# SCH_USB-HUB_2024-08-30.net
KiCad netlist of a schematic drawn in EasyEDA
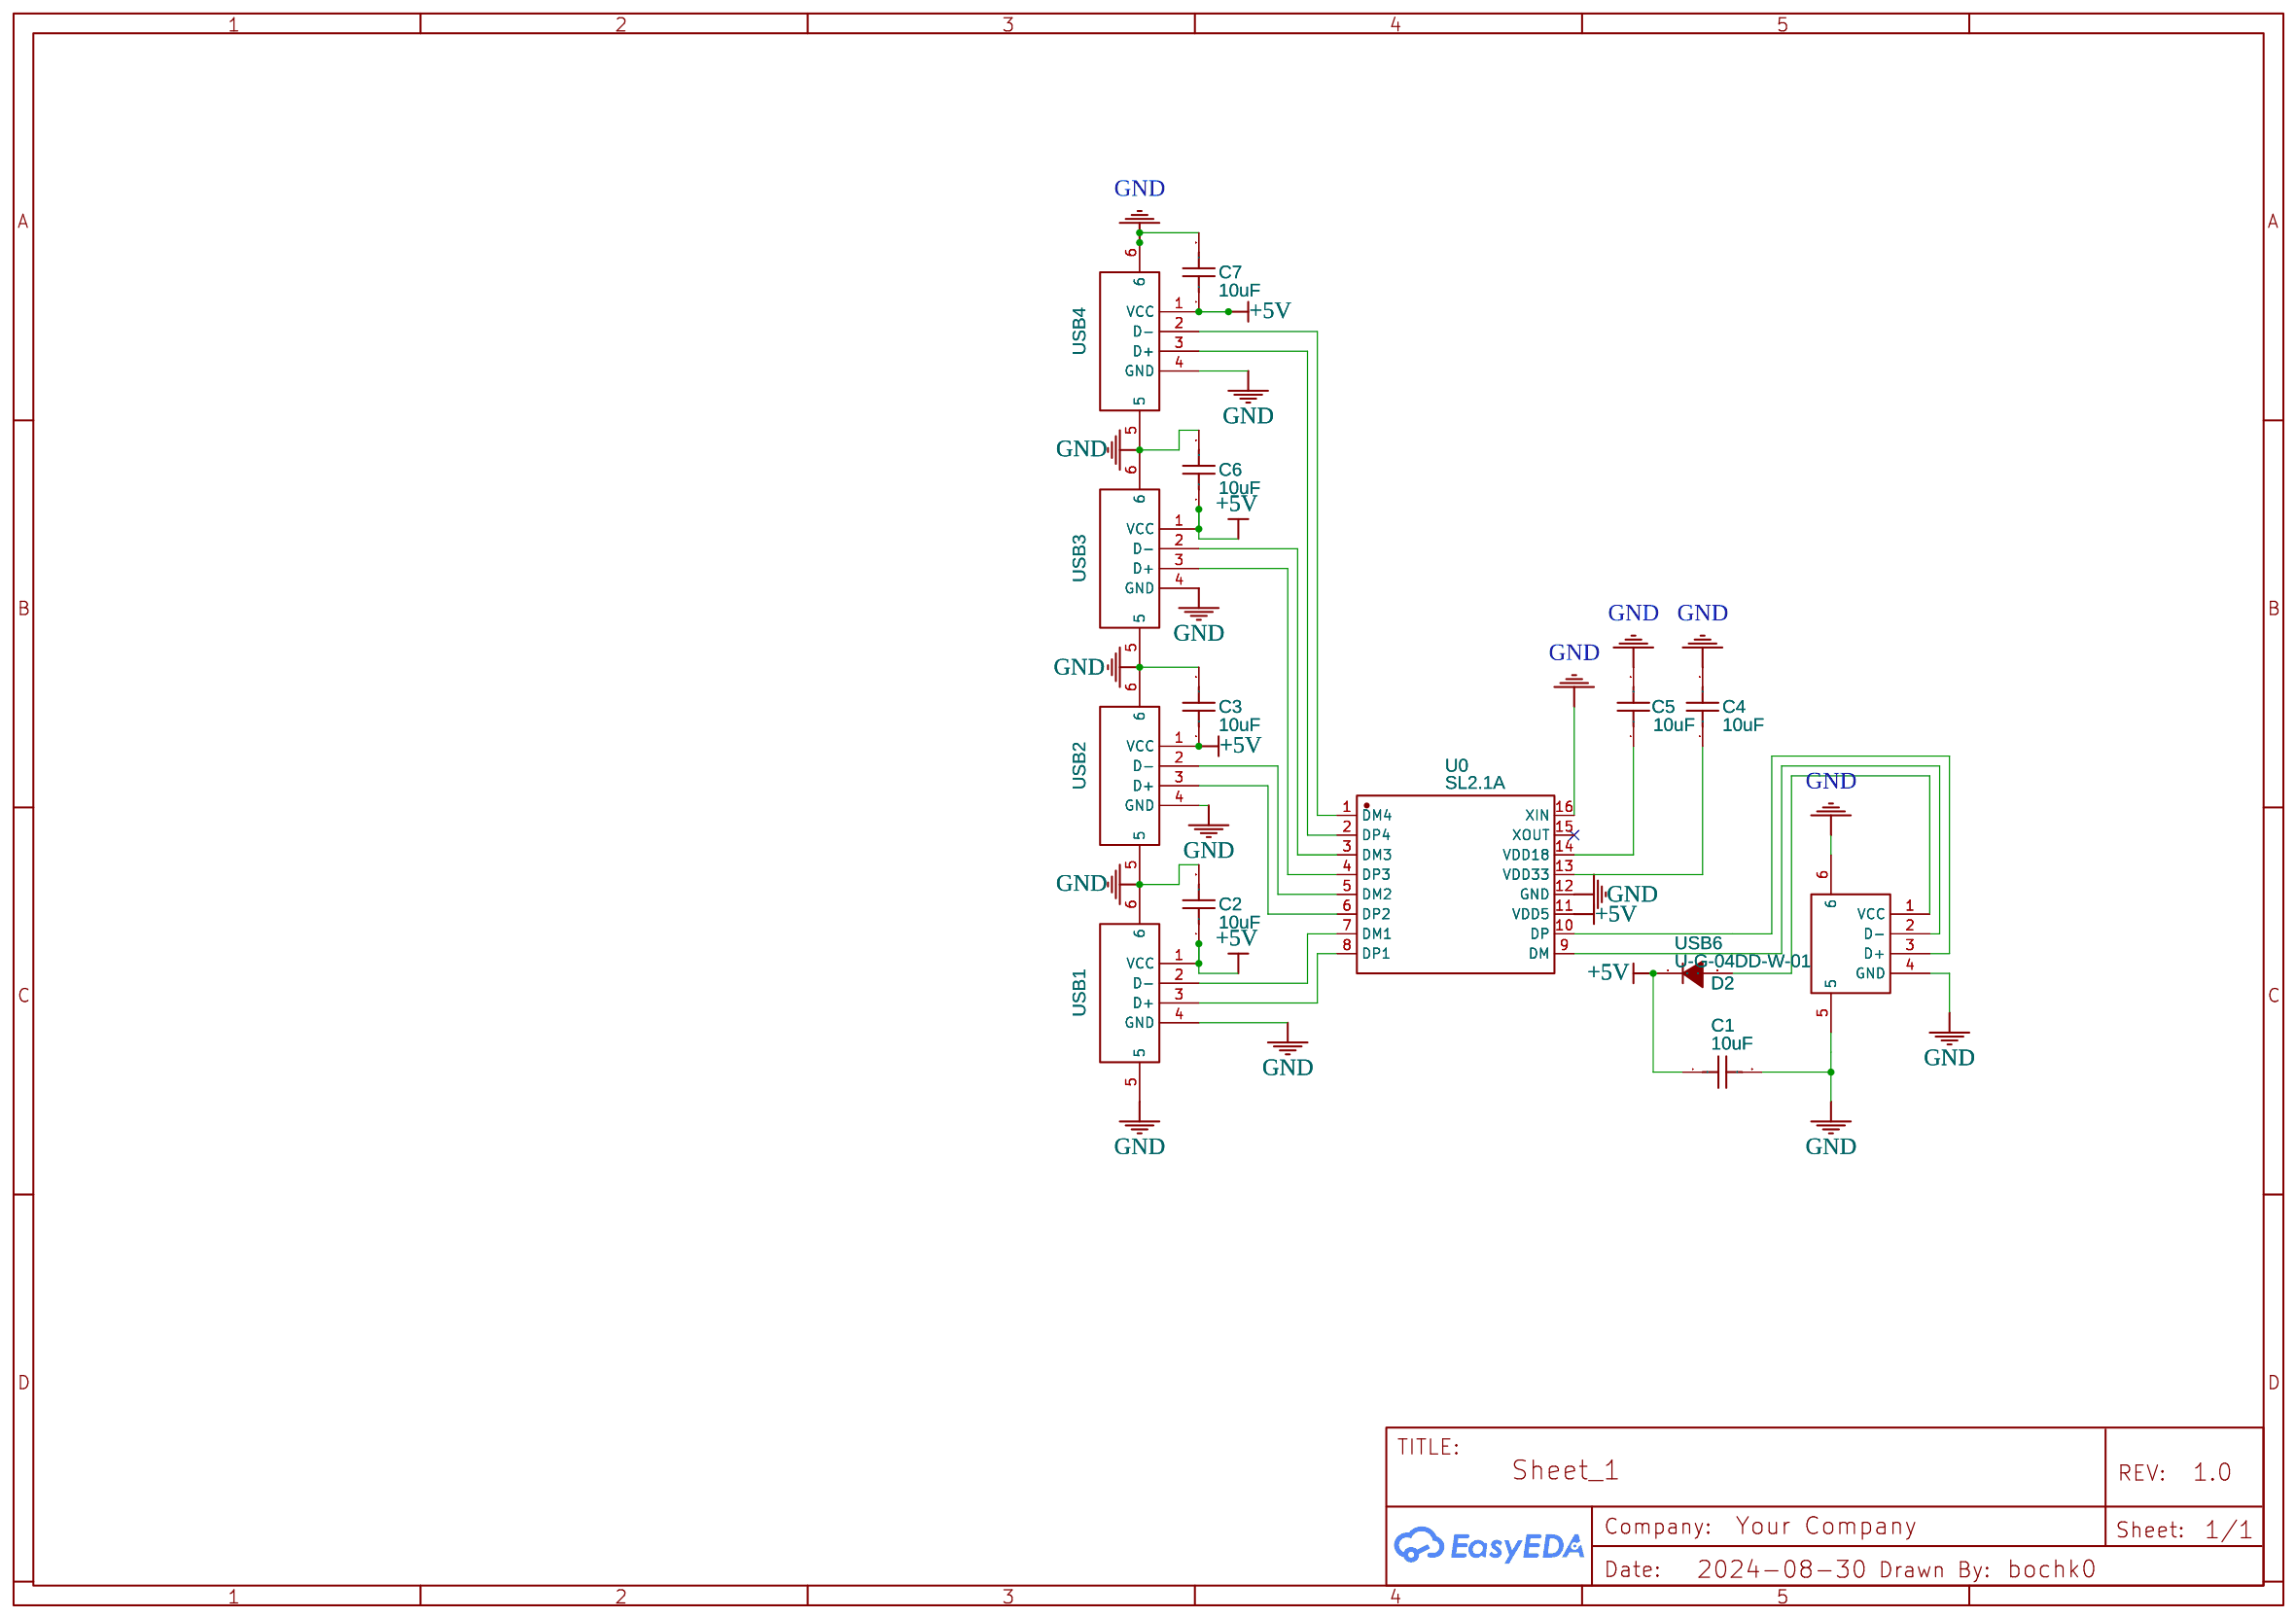
[diagram p0: schematic sheet]

(export (version "E")
  (design (tool "Eeschema 10.0.6"))
  (components
    (comp (ref "C1")
      (value "10uF")
      (fields
        (field (name "Manufacturer Part") "CL10A106KP8NNNC")
        (field (name "Manufacturer") "SAMSUNG(三星)")
      )
      (libsource (lib "") (part "CL10A106KP8NNNC_1"))
    )
    (comp (ref "C2")
      (value "10uF")
      (fields
        (field (name "Manufacturer Part") "CL10A106KP8NNNC")
        (field (name "Manufacturer") "SAMSUNG(三星)")
      )
      (libsource (lib "") (part "CL10A106KP8NNNC"))
    )
    (comp (ref "C3")
      (value "10uF")
      (fields
        (field (name "Manufacturer Part") "CL10A106KP8NNNC")
        (field (name "Manufacturer") "SAMSUNG(三星)")
      )
      (libsource (lib "") (part "CL10A106KP8NNNC"))
    )
    (comp (ref "C4")
      (value "10uF")
      (fields
        (field (name "Manufacturer Part") "CL10A106KP8NNNC")
        (field (name "Manufacturer") "SAMSUNG(三星)")
      )
      (libsource (lib "") (part "CL10A106KP8NNNC"))
    )
    (comp (ref "C5")
      (value "10uF")
      (fields
        (field (name "Manufacturer Part") "CL10A106KP8NNNC")
        (field (name "Manufacturer") "SAMSUNG(三星)")
      )
      (libsource (lib "") (part "CL10A106KP8NNNC"))
    )
    (comp (ref "C6")
      (value "10uF")
      (fields
        (field (name "Manufacturer Part") "CL10A106KP8NNNC")
        (field (name "Manufacturer") "SAMSUNG(三星)")
      )
      (libsource (lib "") (part "CL10A106KP8NNNC"))
    )
    (comp (ref "C7")
      (value "10uF")
      (fields
        (field (name "Manufacturer Part") "CL10A106KP8NNNC")
        (field (name "Manufacturer") "SAMSUNG(三星)")
      )
      (libsource (lib "") (part "CL10A106KP8NNNC"))
    )
    (comp (ref "D2")
      (value "NSR0320MW2T1G")
      (fields (field (name "Manufacturer") "onsemi(安森美)"))
      (libsource (lib "") (part "NSR0320MW2T1G"))
    )
    (comp (ref "U0")
      (value "SL2.1A")
      (fields (field (name "Manufacturer") "CoreChips(和芯润德)"))
      (libsource (lib "") (part "SL2.1A"))
    )
    (comp (ref "USB1")
      (value "USB-AF-90-14.4X13.6-H7.0-DIP")
      (fields (field (name "Manufacturer Part") "903-131A1011D10100") (field (name "Manufacturer") "精拓金"))
      (libsource (lib "") (part "USB-AF-90-14.4X13.6-H7.0-DIP"))
    )
    (comp (ref "USB2")
      (value "USB-AF-90-14.4X13.6-H7.0-DIP")
      (fields (field (name "Manufacturer Part") "903-131A1011D10100") (field (name "Manufacturer") "精拓金"))
      (libsource (lib "") (part "USB-AF-90-14.4X13.6-H7.0-DIP"))
    )
    (comp (ref "USB3")
      (value "USB-AF-90-14.4X13.6-H7.0-DIP")
      (fields (field (name "Manufacturer Part") "903-131A1011D10100") (field (name "Manufacturer") "精拓金"))
      (libsource (lib "") (part "USB-AF-90-14.4X13.6-H7.0-DIP"))
    )
    (comp (ref "USB4")
      (value "USB-AF-90-14.4X13.6-H7.0-DIP")
      (fields (field (name "Manufacturer Part") "903-131A1011D10100") (field (name "Manufacturer") "精拓金"))
      (libsource (lib "") (part "USB-AF-90-14.4X13.6-H7.0-DIP"))
    )
    (comp (ref "USB6")
      (value "U-G-04DD-W-01")
      (fields (field (name "Manufacturer Part") "U-G-O4DD-W-1") (field (name "Manufacturer") "韩国韩荣"))
      (libsource (lib "") (part "U-G-04DD-W-01"))
    )
  )
  (nets
    (net (code "1") (name "+5V") (class "Default")
      (node (ref "C1") (pin "1") (pinfunction "1_1") (pintype "unspecified"))
      (node (ref "C2") (pin "1") (pinfunction "1_1") (pintype "unspecified"))
      (node (ref "C3") (pin "1") (pinfunction "1_1") (pintype "unspecified"))
      (node (ref "C6") (pin "1") (pinfunction "1_1") (pintype "unspecified"))
      (node (ref "C7") (pin "1") (pinfunction "1_1") (pintype "unspecified"))
      (node (ref "D2") (pin "1") (pinfunction "C_1") (pintype "unspecified"))
      (node (ref "U0") (pin "11") (pinfunction "VDD5_11") (pintype "unspecified"))
      (node (ref "USB1") (pin "1") (pinfunction "VCC_1") (pintype "unspecified"))
      (node (ref "USB2") (pin "1") (pinfunction "VCC_1") (pintype "unspecified"))
      (node (ref "USB3") (pin "1") (pinfunction "VCC_1") (pintype "unspecified"))
      (node (ref "USB4") (pin "1") (pinfunction "VCC_1") (pintype "unspecified"))
    )
    (net (code "2") (name "GND") (class "Default")
      (node (ref "C1") (pin "2") (pinfunction "2_2") (pintype "unspecified"))
      (node (ref "C2") (pin "2") (pinfunction "2_2") (pintype "unspecified"))
      (node (ref "C3") (pin "2") (pinfunction "2_2") (pintype "unspecified"))
      (node (ref "C4") (pin "2") (pinfunction "2_2") (pintype "unspecified"))
      (node (ref "C5") (pin "2") (pinfunction "2_2") (pintype "unspecified"))
      (node (ref "C6") (pin "2") (pinfunction "2_2") (pintype "unspecified"))
      (node (ref "C7") (pin "2") (pinfunction "2_2") (pintype "unspecified"))
      (node (ref "U0") (pin "12") (pinfunction "GND_12") (pintype "unspecified"))
      (node (ref "U0") (pin "16") (pinfunction "XIN_16") (pintype "unspecified"))
      (node (ref "USB1") (pin "4") (pinfunction "GND_4") (pintype "unspecified"))
      (node (ref "USB1") (pin "5") (pinfunction "5_5") (pintype "unspecified"))
      (node (ref "USB1") (pin "6") (pinfunction "6_6") (pintype "unspecified"))
      (node (ref "USB2") (pin "4") (pinfunction "GND_4") (pintype "unspecified"))
      (node (ref "USB2") (pin "5") (pinfunction "5_5") (pintype "unspecified"))
      (node (ref "USB2") (pin "6") (pinfunction "6_6") (pintype "unspecified"))
      (node (ref "USB3") (pin "4") (pinfunction "GND_4") (pintype "unspecified"))
      (node (ref "USB3") (pin "5") (pinfunction "5_5") (pintype "unspecified"))
      (node (ref "USB3") (pin "6") (pinfunction "6_6") (pintype "unspecified"))
      (node (ref "USB4") (pin "4") (pinfunction "GND_4") (pintype "unspecified"))
      (node (ref "USB4") (pin "5") (pinfunction "5_5") (pintype "unspecified"))
      (node (ref "USB4") (pin "6") (pinfunction "6_6") (pintype "unspecified"))
      (node (ref "USB6") (pin "4") (pinfunction "GND_4") (pintype "unspecified"))
      (node (ref "USB6") (pin "5") (pinfunction "5_5") (pintype "unspecified"))
      (node (ref "USB6") (pin "6") (pinfunction "6_6") (pintype "unspecified"))
    )
    (net (code "3") (name "Net-(D2-A)") (class "Default")
      (node (ref "D2") (pin "2") (pinfunction "A_2") (pintype "unspecified"))
      (node (ref "USB6") (pin "1") (pinfunction "VCC_1") (pintype "unspecified"))
    )
    (net (code "4") (name "Net-(U0-DM)") (class "Default")
      (node (ref "U0") (pin "9") (pinfunction "DM_9") (pintype "unspecified"))
      (node (ref "USB6") (pin "2") (pinfunction "D-_2") (pintype "unspecified"))
    )
    (net (code "5") (name "Net-(U0-DM1)") (class "Default")
      (node (ref "U0") (pin "7") (pinfunction "DM1_7") (pintype "unspecified"))
      (node (ref "USB1") (pin "2") (pinfunction "D-_2") (pintype "unspecified"))
    )
    (net (code "6") (name "Net-(U0-DM2)") (class "Default")
      (node (ref "U0") (pin "5") (pinfunction "DM2_5") (pintype "unspecified"))
      (node (ref "USB2") (pin "2") (pinfunction "D-_2") (pintype "unspecified"))
    )
    (net (code "7") (name "Net-(U0-DM3)") (class "Default")
      (node (ref "U0") (pin "3") (pinfunction "DM3_3") (pintype "unspecified"))
      (node (ref "USB3") (pin "2") (pinfunction "D-_2") (pintype "unspecified"))
    )
    (net (code "8") (name "Net-(U0-DM4)") (class "Default")
      (node (ref "U0") (pin "1") (pinfunction "DM4_1") (pintype "unspecified"))
      (node (ref "USB4") (pin "2") (pinfunction "D-_2") (pintype "unspecified"))
    )
    (net (code "9") (name "Net-(U0-DP)") (class "Default")
      (node (ref "U0") (pin "10") (pinfunction "DP_10") (pintype "unspecified"))
      (node (ref "USB6") (pin "3") (pinfunction "D+_3") (pintype "unspecified"))
    )
    (net (code "10") (name "Net-(U0-DP1)") (class "Default")
      (node (ref "U0") (pin "8") (pinfunction "DP1_8") (pintype "unspecified"))
      (node (ref "USB1") (pin "3") (pinfunction "D+_3") (pintype "unspecified"))
    )
    (net (code "11") (name "Net-(U0-DP2)") (class "Default")
      (node (ref "U0") (pin "6") (pinfunction "DP2_6") (pintype "unspecified"))
      (node (ref "USB2") (pin "3") (pinfunction "D+_3") (pintype "unspecified"))
    )
    (net (code "12") (name "Net-(U0-DP3)") (class "Default")
      (node (ref "U0") (pin "4") (pinfunction "DP3_4") (pintype "unspecified"))
      (node (ref "USB3") (pin "3") (pinfunction "D+_3") (pintype "unspecified"))
    )
    (net (code "13") (name "Net-(U0-DP4)") (class "Default")
      (node (ref "U0") (pin "2") (pinfunction "DP4_2") (pintype "unspecified"))
      (node (ref "USB4") (pin "3") (pinfunction "D+_3") (pintype "unspecified"))
    )
    (net (code "14") (name "Net-(U0-VDD18)") (class "Default")
      (node (ref "C5") (pin "1") (pinfunction "1_1") (pintype "unspecified"))
      (node (ref "U0") (pin "14") (pinfunction "VDD18_14") (pintype "unspecified"))
    )
    (net (code "15") (name "Net-(U0-VDD33)") (class "Default")
      (node (ref "C4") (pin "1") (pinfunction "1_1") (pintype "unspecified"))
      (node (ref "U0") (pin "13") (pinfunction "VDD33_13") (pintype "unspecified"))
    )
    (net (code "16") (name "unconnected-(U0-XOUT-Pad15)") (class "Default")
      (node (ref "U0") (pin "15") (pinfunction "XOUT_15") (pintype "unspecified+no_connect"))
    )
  )
)
